# TIDA01398_TID_Hardware.net
KiCad netlist of a schematic drawn in Altium Designer
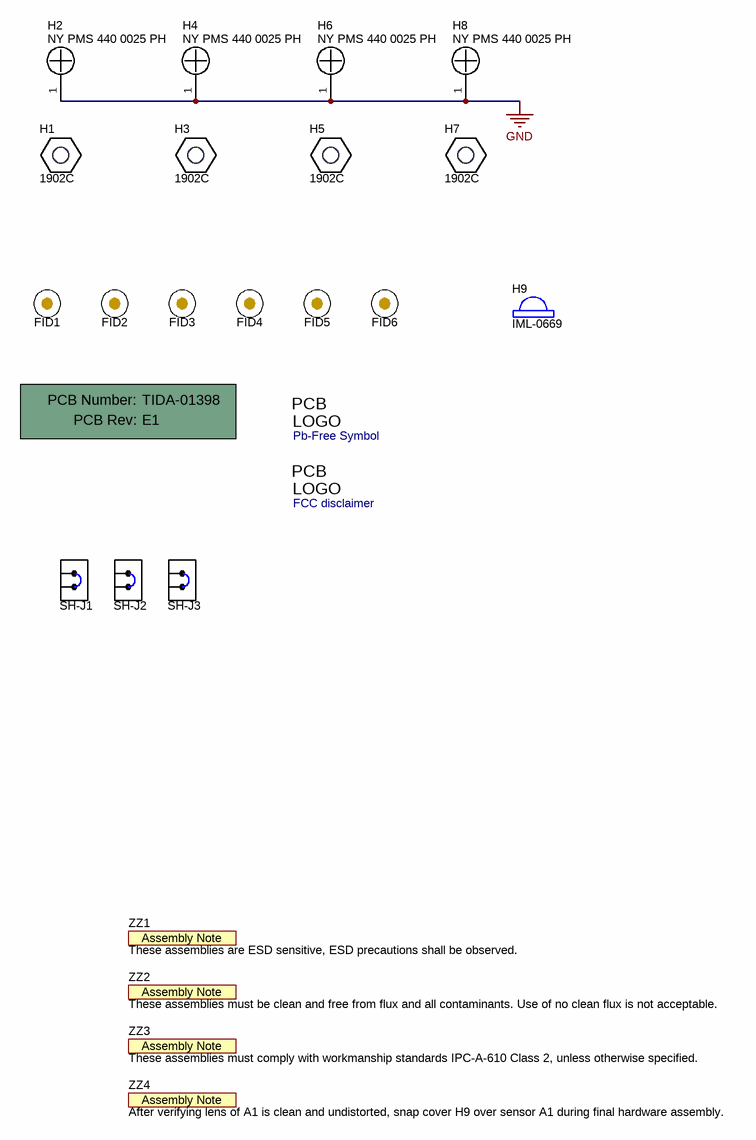
[diagram p0: TIDA01398_TID_Hardware.SchDoc]

(export (version "E")
  (design (tool "Eeschema 10.0.6"))
  (components
    (comp (ref "!PCB1")
      (value "Printed Circuit Board")
      (fields
        (field (name "MANUFACTURER") "Any")
        (field (name "SYMBOLCREATOR") "a0412235")
        (field (name "PUBLISHER") "Texas Instruments")
      )
      (libsource (lib "Hardware") (part "PCB"))
    )
    (comp (ref "FID1")
      (value "Fiducial")
      (footprint "Fiducial10-20")
      (description "Fiducial mark.  There is nothing to buy or mount.")
      (fields (field (name "SYMBOLCREATOR") "codlsc") (field (name "PUBLISHER") "Texas Instruments"))
      (libsource (lib "MiscParts") (part "Fiducial"))
    )
    (comp (ref "FID2")
      (value "Fiducial")
      (footprint "Fiducial10-20")
      (description "Fiducial mark.  There is nothing to buy or mount.")
      (fields (field (name "SYMBOLCREATOR") "codlsc") (field (name "PUBLISHER") "Texas Instruments"))
      (libsource (lib "MiscParts") (part "Fiducial"))
    )
    (comp (ref "FID3")
      (value "Fiducial")
      (footprint "Fiducial10-20")
      (description "Fiducial mark.  There is nothing to buy or mount.")
      (fields (field (name "SYMBOLCREATOR") "codlsc") (field (name "PUBLISHER") "Texas Instruments"))
      (libsource (lib "MiscParts") (part "Fiducial"))
    )
    (comp (ref "FID4")
      (value "Fiducial")
      (footprint "Fiducial10-20")
      (description "Fiducial mark.  There is nothing to buy or mount.")
      (fields (field (name "SYMBOLCREATOR") "codlsc") (field (name "PUBLISHER") "Texas Instruments"))
      (libsource (lib "MiscParts") (part "Fiducial"))
    )
    (comp (ref "FID5")
      (value "Fiducial")
      (footprint "Fiducial10-20")
      (description "Fiducial mark.  There is nothing to buy or mount.")
      (fields (field (name "SYMBOLCREATOR") "codlsc") (field (name "PUBLISHER") "Texas Instruments"))
      (libsource (lib "MiscParts") (part "Fiducial"))
    )
    (comp (ref "FID6")
      (value "Fiducial")
      (footprint "Fiducial10-20")
      (description "Fiducial mark.  There is nothing to buy or mount.")
      (fields (field (name "SYMBOLCREATOR") "codlsc") (field (name "PUBLISHER") "Texas Instruments"))
      (libsource (lib "MiscParts") (part "Fiducial"))
    )
    (comp (ref "H1")
      (value "1902C")
      (footprint "Keystone_1902C")
      (description "Standoff, Hex, 0.5\"L #4-40 Nylon")
      (fields
        (field (name "MANUFACTURER") "Keystone")
        (field (name "PUBLISHER") "Texas Instruments")
        (field (name "SYMBOLCREATOR") "a0412235")
      )
      (libsource (lib "Hardware") (part "1902C"))
    )
    (comp (ref "H2")
      (value "NY PMS 440 0025 PH")
      (footprint "NY PMS 440 0025 PH")
      (description "Machine Screw, Round, #4-40 x 1/4, Nylon, Philips panhead")
      (fields
        (field (name "MANUFACTURER") "B&F Fastener Supply")
        (field (name "DIGIKEYPARTNUMBER") "H542-ND")
        (field (name "SYMBOLCREATOR") "codlsc")
        (field (name "PUBLISHER") "Texas Instruments")
      )
      (libsource (lib "Hardware") (part "NY PMS 440 0025 PH"))
    )
    (comp (ref "H3")
      (value "1902C")
      (footprint "Keystone_1902C")
      (description "Standoff, Hex, 0.5\"L #4-40 Nylon")
      (fields
        (field (name "MANUFACTURER") "Keystone")
        (field (name "PUBLISHER") "Texas Instruments")
        (field (name "SYMBOLCREATOR") "a0412235")
      )
      (libsource (lib "Hardware") (part "1902C"))
    )
    (comp (ref "H4")
      (value "NY PMS 440 0025 PH")
      (footprint "NY PMS 440 0025 PH")
      (description "Machine Screw, Round, #4-40 x 1/4, Nylon, Philips panhead")
      (fields
        (field (name "MANUFACTURER") "B&F Fastener Supply")
        (field (name "DIGIKEYPARTNUMBER") "H542-ND")
        (field (name "SYMBOLCREATOR") "codlsc")
        (field (name "PUBLISHER") "Texas Instruments")
      )
      (libsource (lib "Hardware") (part "NY PMS 440 0025 PH"))
    )
    (comp (ref "H5")
      (value "1902C")
      (footprint "Keystone_1902C")
      (description "Standoff, Hex, 0.5\"L #4-40 Nylon")
      (fields
        (field (name "MANUFACTURER") "Keystone")
        (field (name "PUBLISHER") "Texas Instruments")
        (field (name "SYMBOLCREATOR") "a0412235")
      )
      (libsource (lib "Hardware") (part "1902C"))
    )
    (comp (ref "H6")
      (value "NY PMS 440 0025 PH")
      (footprint "NY PMS 440 0025 PH")
      (description "Machine Screw, Round, #4-40 x 1/4, Nylon, Philips panhead")
      (fields
        (field (name "MANUFACTURER") "B&F Fastener Supply")
        (field (name "DIGIKEYPARTNUMBER") "H542-ND")
        (field (name "SYMBOLCREATOR") "codlsc")
        (field (name "PUBLISHER") "Texas Instruments")
      )
      (libsource (lib "Hardware") (part "NY PMS 440 0025 PH"))
    )
    (comp (ref "H7")
      (value "1902C")
      (footprint "Keystone_1902C")
      (description "Standoff, Hex, 0.5\"L #4-40 Nylon")
      (fields
        (field (name "MANUFACTURER") "Keystone")
        (field (name "PUBLISHER") "Texas Instruments")
        (field (name "SYMBOLCREATOR") "a0412235")
      )
      (libsource (lib "Hardware") (part "1902C"))
    )
    (comp (ref "H8")
      (value "NY PMS 440 0025 PH")
      (footprint "NY PMS 440 0025 PH")
      (description "Machine Screw, Round, #4-40 x 1/4, Nylon, Philips panhead")
      (fields
        (field (name "MANUFACTURER") "B&F Fastener Supply")
        (field (name "DIGIKEYPARTNUMBER") "H542-ND")
        (field (name "SYMBOLCREATOR") "codlsc")
        (field (name "PUBLISHER") "Texas Instruments")
      )
      (libsource (lib "Hardware") (part "NY PMS 440 0025 PH"))
    )
    (comp (ref "H9")
      (value "IML-0669")
      (footprint "Murata_IML-0669")
      (description "Lens, Ceiling Mount, TH")
      (fields
        (field (name "MANUFACTURER") "MuRata")
        (field (name "SYMBOLCREATOR") "Altium")
        (field (name "PUBLISHER") "Texas Instruments")
      )
      (libsource (lib "Hardware") (part "IML-0669"))
    )
    (comp (ref "Logo2")
      (value "FCC disclaimer")
      (footprint "FCC_disclaimer_stacked")
      (description "FCC_disclaimer")
      (fields (field (name "SYMBOLCREATOR") "codlsc") (field (name "PUBLISHER") "Texas Instruments"))
      (libsource (lib "Logos") (part "FCC_disclaimer"))
    )
    (comp (ref "Logo3")
      (value "Pb-Free Symbol")
      (footprint "Pb-Free_Overlay_Small")
      (fields (field (name "SYMBOLCREATOR") "a0412235") (field (name "PUBLISHER") "Texas Instruments"))
      (libsource (lib "Logos") (part "Pb-Free"))
    )
    (comp (ref "SH-J1")
      (value "969102-0000-DA")
      (footprint "SNT-100-BK-G")
      (description "Shunt, 100mil, Gold plated, Black")
      (fields
        (field (name "MANUFACTURER") "3M")
        (field (name "ALTERNATE PARTNUMBER") "SNT-100-BK-G")
        (field (name "PUBLISHER") "Texas Instruments")
      )
      (libsource (lib "Hardware") (part "969102-0000-DA"))
    )
    (comp (ref "SH-J2")
      (value "969102-0000-DA")
      (footprint "SNT-100-BK-G")
      (description "Shunt, 100mil, Gold plated, Black")
      (fields
        (field (name "MANUFACTURER") "3M")
        (field (name "ALTERNATE PARTNUMBER") "SNT-100-BK-G")
        (field (name "PUBLISHER") "Texas Instruments")
      )
      (libsource (lib "Hardware") (part "969102-0000-DA"))
    )
    (comp (ref "SH-J3")
      (value "969102-0000-DA")
      (footprint "SNT-100-BK-G")
      (description "Shunt, 100mil, Gold plated, Black")
      (fields
        (field (name "MANUFACTURER") "3M")
        (field (name "ALTERNATE PARTNUMBER") "SNT-100-BK-G")
        (field (name "PUBLISHER") "Texas Instruments")
      )
      (libsource (lib "Hardware") (part "969102-0000-DA"))
    )
    (comp (ref "ZZ1")
      (value "These assemblies are ESD sensitive, ESD precautions shall be observed.")
      (footprint "AssemblyNote")
      (fields (field (name "SYMBOLCREATOR") "codlsc") (field (name "PUBLISHER") "Texas Instruments"))
      (libsource (lib "Hardware") (part "AssemblyNote"))
    )
    (comp (ref "ZZ2")
      (value "These assemblies must be clean and free from flux and all contaminants. Use of no clean flux is not acceptable.")
      (footprint "AssemblyNote")
      (fields (field (name "SYMBOLCREATOR") "codlsc") (field (name "PUBLISHER") "Texas Instruments"))
      (libsource (lib "Hardware") (part "AssemblyNote"))
    )
    (comp (ref "ZZ3")
      (value "These assemblies must comply with workmanship standards IPC-A-610 Class 2, unless otherwise specified.")
      (footprint "AssemblyNote")
      (fields (field (name "SYMBOLCREATOR") "codlsc") (field (name "PUBLISHER") "Texas Instruments"))
      (libsource (lib "Hardware") (part "AssemblyNote"))
    )
    (comp (ref "ZZ4")
      (value "After verifying lens of A1 is clean and undistorted, snap cover H9 over sensor A1 during final hardware assembly.")
      (footprint "AssemblyNote")
      (fields (field (name "SYMBOLCREATOR") "codlsc") (field (name "PUBLISHER") "Texas Instruments"))
      (libsource (lib "Hardware") (part "AssemblyNote"))
    )
  )
  (nets
    (net (code "1") (name "GND") (class "Default")
      (node (ref "H2") (pin "1") (pinfunction "1_1") (pintype "passive"))
      (node (ref "H4") (pin "1") (pinfunction "1_1") (pintype "passive"))
      (node (ref "H6") (pin "1") (pinfunction "1_1") (pintype "passive"))
      (node (ref "H8") (pin "1") (pinfunction "1_1") (pintype "passive"))
    )
  )
)
